# MCU.net
KiCad netlist of a schematic drawn in Altium Designer
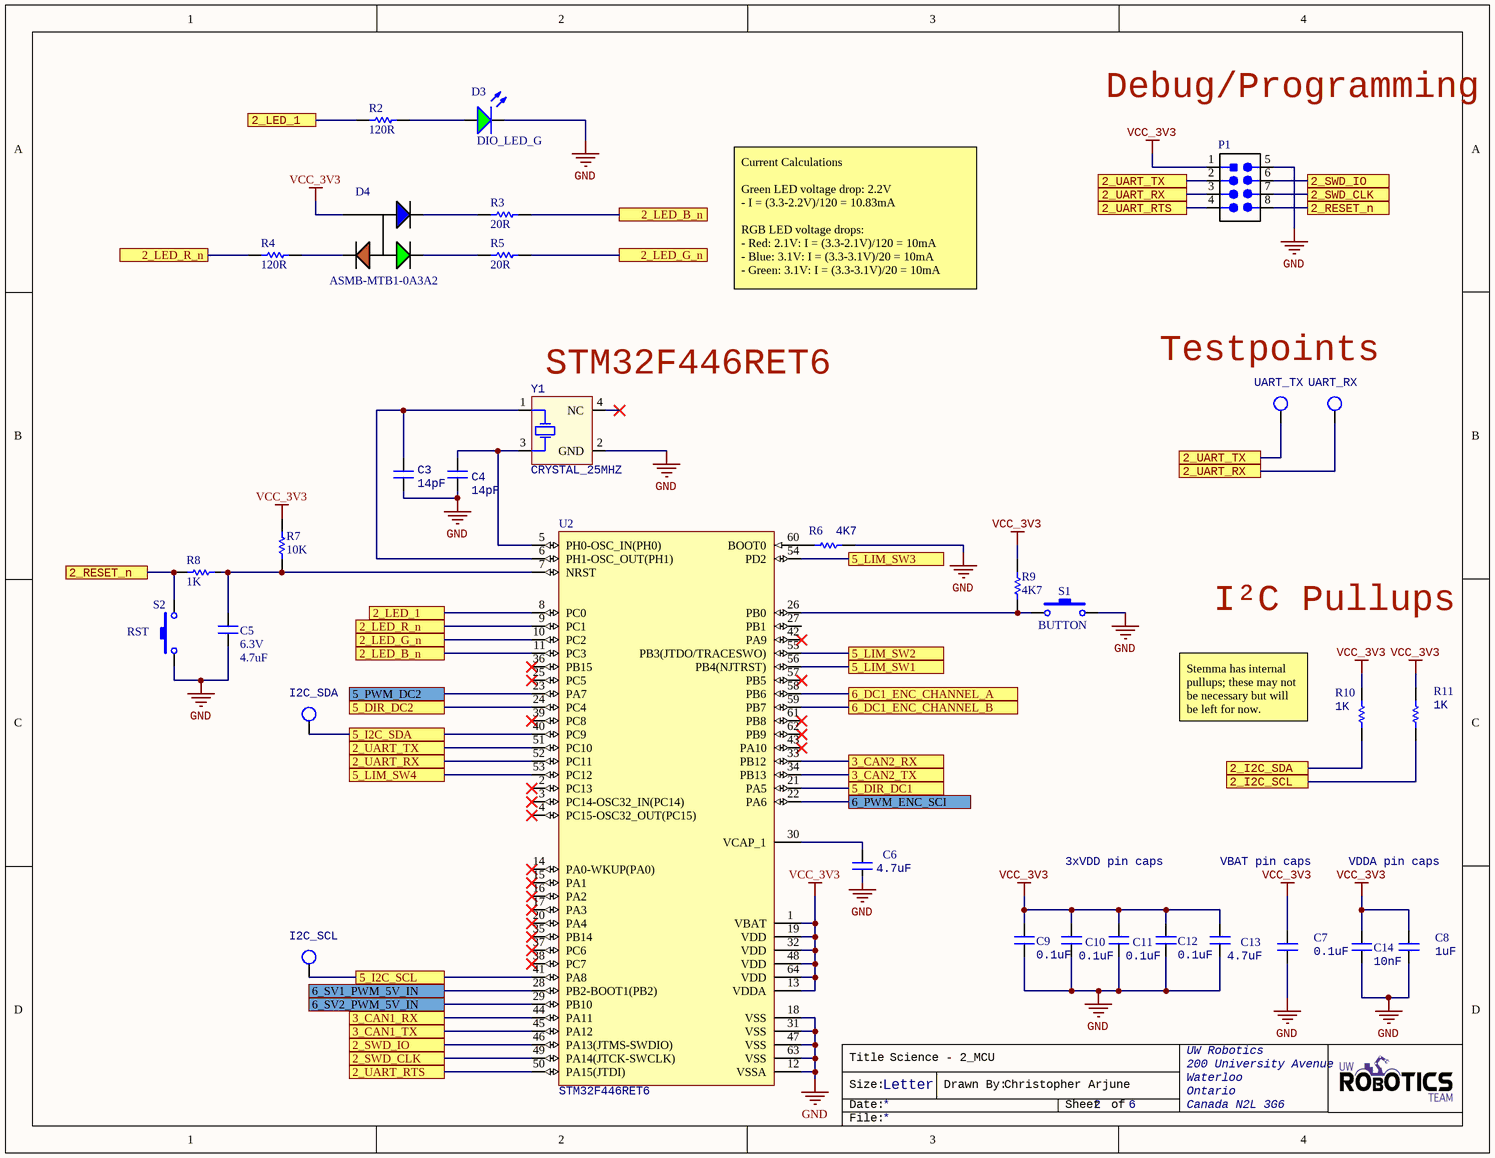
[diagram p0: MCU.SchDoc]

(export (version "E")
  (design (tool "Eeschema 10.0.6"))
  (components
    (comp (ref "C3")
      (value "14pF")
      (description "CAP CER 14PF 50V C0G/NP0 0603")
      (fields (field (name "TOLERANCE") "5%") (field (name "Comment") "CAP_14pF_50V_0603"))
      (libsource (lib "UWRT_Schematic_Library_2020") (part "CAP_14pF_50V_0603"))
    )
    (comp (ref "C4")
      (value "14pF")
      (description "CAP CER 14PF 50V C0G/NP0 0603")
      (fields (field (name "TOLERANCE") "5%") (field (name "Comment") "CAP_14pF_50V_0603"))
      (libsource (lib "UWRT_Schematic_Library_2020") (part "CAP_14pF_50V_0603"))
    )
    (comp (ref "C5")
      (value "4.7uF")
      (footprint "CAPC0603(1608)55_N")
      (description "CAP CER 4.7UF 6.3V X5R 0603")
      (fields (field (name "VOLTAGE RATING") "6.3V") (field (name "Comment") "CAP_4.7uF_0603"))
      (libsource (lib "UWRT_Schematic_Library_2020") (part "CAP_4.7uF_0603"))
    )
    (comp (ref "C6")
      (value "4.7uF")
      (footprint "CAPC0603(1608)55_N")
      (description "CAP CER 4.7UF 6.3V X5R 0603")
      (fields (field (name "MANUFACTURER") "Yageo") (field (name "MPN") "CC0603KRX5R5BB475"))
      (libsource (lib "UWRT_Schematic_Library_2020") (part "CAP_4.7uF_0603"))
    )
    (comp (ref "C7")
      (value "0.1uF")
      (footprint "CAPC0603(1608)55_N")
      (description "CAP CER 0.1UF 16V X7R 0603")
      (fields (field (name "MANUFACTURER") "Yageo") (field (name "MPN") "CC0603KRX7R7BB104"))
      (libsource (lib "UWRT_Schematic_Library_2020") (part "CAP_0.1uF_16V_0603"))
    )
    (comp (ref "C8")
      (value "1uF")
      (footprint "CAPC0603(1608)55_N")
      (description "CAP CER 1UF 16V Y5V 0603")
      (fields (field (name "MANUFACTURER") "Yageo") (field (name "MPN") "CC0603ZRY5V7BB105"))
      (libsource (lib "UWRT_Schematic_Library_2020") (part "CAP_1uF_16V_0603"))
    )
    (comp (ref "C9")
      (value "0.1uF")
      (footprint "CAPC0603(1608)55_N")
      (description "CAP CER 0.1UF 16V X7R 0603")
      (fields (field (name "MANUFACTURER") "Yageo") (field (name "MPN") "CC0603KRX7R7BB104"))
      (libsource (lib "UWRT_Schematic_Library_2020") (part "CAP_0.1uF_16V_0603"))
    )
    (comp (ref "C10")
      (value "0.1uF")
      (footprint "CAPC0603(1608)55_N")
      (description "CAP CER 0.1UF 16V X7R 0603")
      (fields (field (name "MANUFACTURER") "Yageo") (field (name "MPN") "CC0603KRX7R7BB104"))
      (libsource (lib "UWRT_Schematic_Library_2020") (part "CAP_0.1uF_16V_0603"))
    )
    (comp (ref "C11")
      (value "0.1uF")
      (footprint "CAPC0603(1608)55_N")
      (description "CAP CER 0.1UF 16V X7R 0603")
      (fields (field (name "MANUFACTURER") "Yageo") (field (name "MPN") "CC0603KRX7R7BB104"))
      (libsource (lib "UWRT_Schematic_Library_2020") (part "CAP_0.1uF_16V_0603"))
    )
    (comp (ref "C12")
      (value "0.1uF")
      (footprint "CAPC0603(1608)55_N")
      (description "CAP CER 0.1UF 16V X7R 0603")
      (fields (field (name "MANUFACTURER") "Yageo") (field (name "MPN") "CC0603KRX7R7BB104"))
      (libsource (lib "UWRT_Schematic_Library_2020") (part "CAP_0.1uF_16V_0603"))
    )
    (comp (ref "C13")
      (value "4.7uF")
      (footprint "CAPC0603(1608)55_N")
      (description "CAP CER 4.7UF 6.3V X5R 0603")
      (fields (field (name "MANUFACTURER") "Yageo") (field (name "MPN") "CC0603KRX5R5BB475"))
      (libsource (lib "UWRT_Schematic_Library_2020") (part "CAP_4.7uF_0603"))
    )
    (comp (ref "C14")
      (value "10nF")
      (footprint "CAPC0603(1608)55_N")
      (description "CAP CER 10000PF 16V X7R 0603")
      (fields (field (name "MANUFACTURER") "Yageo") (field (name "MPN") "CC0603KRX7R7BB103"))
      (libsource (lib "UWRT_Schematic_Library_2020") (part "CAP_10nF_0603"))
    )
    (comp (ref "D3")
      (value "DIO_LED_G")
      (footprint "LED_0805_LINE")
      (description "LED GREEN DIFFUSED 0805 SMD")
      (fields (field (name "MANUFACTURER") "OSRAM") (field (name "MPN") "LG R971-KN-1"))
      (libsource (lib "UWRT_Schematic_Library_2020") (part "DIO_LED_G"))
    )
    (comp (ref "D4")
      (value "LED_RGB")
      (footprint "LED_RGB")
      (description "LED RGB DIFFUSED 4PLCC SMD")
      (fields (field (name "MANUFACTURER PART NUMBER 1") "ASMB-MTB1-0A3A2"))
      (libsource (lib "UWRT_Schematic_Library_2020") (part "LED_RGB"))
    )
    (comp (ref "I2C_SCL")
      (value "TESTPOINT_LOOP")
      (footprint "TESTPOINT_LOOP")
      (description "Loop testpoint through-hole pad")
      (fields (field (name "MANUFACTURER") "Keystone Electronics"))
      (libsource (lib "UWRT_Schematic_Library_2020") (part "TESTPOINT_LOOP"))
    )
    (comp (ref "I2C_SDA")
      (value "TESTPOINT_LOOP")
      (footprint "TESTPOINT_LOOP")
      (description "Loop testpoint through-hole pad")
      (fields (field (name "MANUFACTURER") "Keystone Electronics"))
      (libsource (lib "UWRT_Schematic_Library_2020") (part "TESTPOINT_LOOP"))
    )
    (comp (ref "P1")
      (value "HEADER 4X2")
      (footprint "HEADER_2X4")
      (description "CONN HEADER VERT 8POS 2.54MM")
      (libsource (lib "UWRT_Schematic_Library_2020") (part "HEADER 4X2"))
    )
    (comp (ref "R2")
      (value "120R")
      (footprint "RESC0603(1608)_N")
      (description "RES SMD 120 OHM 5% 1/10W 0603")
      (fields (field (name "MANUFACTURER") "Yageo") (field (name "TOLERANCE") "5%"))
      (libsource (lib "UWRT_Schematic_Library_2020") (part "RES_120R_0603"))
    )
    (comp (ref "R3")
      (value "20R")
      (footprint "RESC0603(1608)_N")
      (description "RES SMD 20 OHM 5% 1/10W 0603")
      (fields (field (name "MANUFACTURER") "Yageo") (field (name "MPN") "RC0603JR-0720RL"))
      (libsource (lib "UWRT_Schematic_Library_2020") (part "RES_20R_0603"))
    )
    (comp (ref "R4")
      (value "120R")
      (footprint "RESC0603(1608)_N")
      (description "RES SMD 120 OHM 5% 1/10W 0603")
      (fields (field (name "MANUFACTURER") "Yageo") (field (name "MPN") "RC0603JR-07120RL"))
      (libsource (lib "UWRT_Schematic_Library_2020") (part "RES_120R_0603"))
    )
    (comp (ref "R5")
      (value "20R")
      (footprint "RESC0603(1608)_N")
      (description "RES SMD 20 OHM 5% 1/10W 0603")
      (fields (field (name "MANUFACTURER") "Yageo") (field (name "MPN") "RC0603JR-0720RL"))
      (libsource (lib "UWRT_Schematic_Library_2020") (part "RES_20R_0603"))
    )
    (comp (ref "R6")
      (value "4K7")
      (footprint "RESC0603(1608)_N")
      (description "RES SMD 4.7K OHM 5% 1/10W 0603")
      (fields (field (name "MANUFACTURER") "Yageo") (field (name "TOLERANCE") "5%"))
      (libsource (lib "UWRT_Schematic_Library_2020") (part "RES_4K7_0603"))
    )
    (comp (ref "R7")
      (value "10K")
      (footprint "RESC0603(1608)_N")
      (description "RES SMD 10K OHM 5% 1/10W 0603")
      (fields (field (name "TOLERANCE") "5%") (field (name "Comment") "RES_10K_0603"))
      (libsource (lib "UWRT_Schematic_Library_2020") (part "RES_10K_0603"))
    )
    (comp (ref "R8")
      (value "1K")
      (footprint "RESC0603(1608)_N")
      (description "RES SMD 1K OHM 5% 1/10W 0603")
      (fields (field (name "TOLERANCE") "5%") (field (name "Comment") "RES_1K_0603"))
      (libsource (lib "UWRT_Schematic_Library_2020") (part "RES_1K_0603"))
    )
    (comp (ref "R9")
      (value "4K7")
      (footprint "RESC0603(1608)_N")
      (description "RES SMD 4.7K OHM 5% 1/10W 0603")
      (fields (field (name "MANUFACTURER") "Yageo") (field (name "TOLERANCE") "5%"))
      (libsource (lib "UWRT_Schematic_Library_2020") (part "RES_4K7_0603"))
    )
    (comp (ref "R10")
      (value "1K")
      (footprint "RESC0603(1608)_N")
      (description "RES SMD 4.7K OHM 5% 1/10W 0603")
      (fields (field (name "MANUFACTURER") "Yageo") (field (name "TOLERANCE") "5%"))
      (libsource (lib "UWRT_Schematic_Library_2020") (part "RES_4K7_0603"))
    )
    (comp (ref "R11")
      (value "1K")
      (footprint "RESC0603(1608)_N")
      (description "RES SMD 4.7K OHM 5% 1/10W 0603")
      (fields (field (name "MANUFACTURER") "Yageo") (field (name "TOLERANCE") "5%"))
      (libsource (lib "UWRT_Schematic_Library_2020") (part "RES_4K7_0603"))
    )
    (comp (ref "S1")
      (value "BUTTON")
      (footprint "B3U-1100P")
      (description "Tactile Switch (Grey)")
      (fields (field (name "MPN") "B3U-1100P") (field (name "MANUFACTURER") "Omron Electronics Inc-EMC Div"))
      (libsource (lib "UWRT_Schematic_Library_2020") (part "SW_TACTILE"))
    )
    (comp (ref "S2")
      (value "RST")
      (footprint "PTS830GM140")
      (description "Power Switch (Red)")
      (fields (field (name "MPN") "PTS830GM140 SMTR LFS") (field (name "MANUFACTURER") "C&K"))
      (libsource (lib "UWRT_Schematic_Library_2020") (part "SW_PWR"))
    )
    (comp (ref "U2")
      (value "STM32F446RET6")
      (footprint "STM-LQFP64_L")
      (libsource (lib "UWRT_Schematic_Library_2020") (part "MCU_STM32F446RET6"))
    )
    (comp (ref "UART_RX")
      (value "TESTPOINT_LOOP")
      (footprint "TESTPOINT_LOOP")
      (description "Loop testpoint through-hole pad")
      (fields (field (name "MANUFACTURER") "Keystone Electronics"))
      (libsource (lib "UWRT_Schematic_Library_2020") (part "TESTPOINT_LOOP"))
    )
    (comp (ref "UART_TX")
      (value "TESTPOINT_LOOP")
      (footprint "TESTPOINT_LOOP")
      (description "Loop testpoint through-hole pad")
      (fields (field (name "MANUFACTURER") "Keystone Electronics"))
      (libsource (lib "UWRT_Schematic_Library_2020") (part "TESTPOINT_LOOP"))
    )
    (comp (ref "Y1")
      (value "CRYSTAL_25MHZ")
      (description "CRYSTAL 25.0000MHZ 12PF SMD")
      (libsource (lib "UWRT_Schematic_Library_2020") (part "CRYSTAL_25MHZ"))
    )
  )
  (nets
    (net (code "1") (name "/2_I2C_SCL") (class "Default")
      (node (ref "R11") (pin "1") (pinfunction "1_1") (pintype "passive"))
    )
    (net (code "2") (name "/2_I2C_SDA") (class "Default")
      (node (ref "R10") (pin "1") (pinfunction "1_1") (pintype "passive"))
    )
    (net (code "3") (name "/2_LED_1") (class "Default")
      (node (ref "R2") (pin "1") (pinfunction "1_1") (pintype "passive"))
      (node (ref "U2") (pin "8") (pinfunction "PC0_8") (pintype "bidirectional"))
    )
    (net (code "4") (name "/2_LED_B_n") (class "Default")
      (node (ref "R3") (pin "2") (pinfunction "2_2") (pintype "passive"))
      (node (ref "U2") (pin "11") (pinfunction "PC3_11") (pintype "bidirectional"))
    )
    (net (code "5") (name "/2_LED_G_n") (class "Default")
      (node (ref "R5") (pin "2") (pinfunction "2_2") (pintype "passive"))
      (node (ref "U2") (pin "10") (pinfunction "PC2_10") (pintype "bidirectional"))
    )
    (net (code "6") (name "/2_LED_R_n") (class "Default")
      (node (ref "R4") (pin "1") (pinfunction "1_1") (pintype "passive"))
      (node (ref "U2") (pin "9") (pinfunction "PC1_9") (pintype "bidirectional"))
    )
    (net (code "7") (name "/2_RESET_n") (class "Default")
      (node (ref "P1") (pin "8") (pinfunction "4_8") (pintype "passive"))
      (node (ref "R8") (pin "1") (pinfunction "1_1") (pintype "passive"))
      (node (ref "S2") (pin "2") (pinfunction "2_2") (pintype "passive"))
    )
    (net (code "8") (name "/2_SWD_CLK") (class "Default")
      (node (ref "P1") (pin "7") (pinfunction "3_7") (pintype "passive"))
      (node (ref "U2") (pin "49") (pinfunction "PA14(JTCK-SWCLK)_49") (pintype "bidirectional"))
    )
    (net (code "9") (name "/2_SWD_IO") (class "Default")
      (node (ref "P1") (pin "6") (pinfunction "2_6") (pintype "passive"))
      (node (ref "U2") (pin "46") (pinfunction "PA13(JTMS-SWDIO)_46") (pintype "bidirectional"))
    )
    (net (code "10") (name "/2_UART_RTS") (class "Default")
      (node (ref "P1") (pin "4") (pinfunction "4_4") (pintype "passive"))
      (node (ref "U2") (pin "50") (pinfunction "PA15(JTDI)_50") (pintype "bidirectional"))
    )
    (net (code "11") (name "/2_UART_RX") (class "Default")
      (node (ref "P1") (pin "3") (pinfunction "3_3") (pintype "passive"))
      (node (ref "U2") (pin "52") (pinfunction "PC11_52") (pintype "bidirectional"))
      (node (ref "UART_RX") (pin "1") (pintype "passive"))
    )
    (net (code "12") (name "/2_UART_TX") (class "Default")
      (node (ref "P1") (pin "2") (pinfunction "2_2") (pintype "passive"))
      (node (ref "U2") (pin "51") (pinfunction "PC10_51") (pintype "bidirectional"))
      (node (ref "UART_TX") (pin "1") (pintype "passive"))
    )
    (net (code "13") (name "/3_CAN1_RX") (class "Default")
      (node (ref "U2") (pin "44") (pinfunction "PA11_44") (pintype "bidirectional"))
    )
    (net (code "14") (name "/3_CAN1_TX") (class "Default")
      (node (ref "U2") (pin "45") (pinfunction "PA12_45") (pintype "bidirectional"))
    )
    (net (code "15") (name "/3_CAN2_RX") (class "Default")
      (node (ref "U2") (pin "33") (pinfunction "PB12_33") (pintype "bidirectional"))
    )
    (net (code "16") (name "/3_CAN2_TX") (class "Default")
      (node (ref "U2") (pin "34") (pinfunction "PB13_34") (pintype "bidirectional"))
    )
    (net (code "17") (name "/5_DIR_DC1") (class "Default")
      (node (ref "U2") (pin "21") (pinfunction "PA5_21") (pintype "bidirectional"))
    )
    (net (code "18") (name "/5_DIR_DC2") (class "Default")
      (node (ref "U2") (pin "24") (pinfunction "PC4_24") (pintype "bidirectional"))
    )
    (net (code "19") (name "/5_I2C_SCL") (class "Default")
      (node (ref "I2C_SCL") (pin "1") (pintype "passive"))
      (node (ref "U2") (pin "41") (pinfunction "PA8_41") (pintype "bidirectional"))
    )
    (net (code "20") (name "/5_I2C_SDA") (class "Default")
      (node (ref "I2C_SDA") (pin "1") (pintype "passive"))
      (node (ref "U2") (pin "40") (pinfunction "PC9_40") (pintype "bidirectional"))
    )
    (net (code "21") (name "/5_LIM_SW1") (class "Default")
      (node (ref "U2") (pin "56") (pinfunction "PB4(NJTRST)_56") (pintype "bidirectional"))
    )
    (net (code "22") (name "/5_LIM_SW2") (class "Default")
      (node (ref "U2") (pin "55") (pinfunction "PB3(JTDO/TRACESWO)_55") (pintype "bidirectional"))
    )
    (net (code "23") (name "/5_LIM_SW3") (class "Default")
      (node (ref "U2") (pin "54") (pinfunction "PD2_54") (pintype "bidirectional"))
    )
    (net (code "24") (name "/5_LIM_SW4") (class "Default")
      (node (ref "U2") (pin "53") (pinfunction "PC12_53") (pintype "bidirectional"))
    )
    (net (code "25") (name "/5_PWM_DC2") (class "Default")
      (node (ref "U2") (pin "23") (pinfunction "PA7_23") (pintype "bidirectional"))
    )
    (net (code "26") (name "/6_DC1_ENC_CHANNEL_A") (class "Default")
      (node (ref "U2") (pin "58") (pinfunction "PB6_58") (pintype "bidirectional"))
    )
    (net (code "27") (name "/6_DC1_ENC_CHANNEL_B") (class "Default")
      (node (ref "U2") (pin "59") (pinfunction "PB7_59") (pintype "bidirectional"))
    )
    (net (code "28") (name "/6_PWM_ENC_SCI") (class "Default")
      (node (ref "U2") (pin "22") (pinfunction "PA6_22") (pintype "bidirectional"))
    )
    (net (code "29") (name "/6_SV1_PWM_5V_IN") (class "Default")
      (node (ref "U2") (pin "28") (pinfunction "PB2-BOOT1(PB2)_28") (pintype "bidirectional"))
    )
    (net (code "30") (name "/6_SV2_PWM_5V_IN") (class "Default")
      (node (ref "U2") (pin "29") (pinfunction "PB10_29") (pintype "bidirectional"))
    )
    (net (code "31") (name "GND") (class "Default")
      (node (ref "C10") (pin "1") (pinfunction "1_1") (pintype "passive"))
      (node (ref "C11") (pin "1") (pinfunction "1_1") (pintype "passive"))
      (node (ref "C12") (pin "1") (pinfunction "1_1") (pintype "passive"))
      (node (ref "C13") (pin "1") (pinfunction "1_1") (pintype "passive"))
      (node (ref "C14") (pin "1") (pinfunction "1_1") (pintype "passive"))
      (node (ref "C3") (pin "1") (pinfunction "1_1") (pintype "passive"))
      (node (ref "C4") (pin "1") (pinfunction "1_1") (pintype "passive"))
      (node (ref "C5") (pin "2") (pinfunction "2_2") (pintype "passive"))
      (node (ref "C6") (pin "1") (pinfunction "1_1") (pintype "passive"))
      (node (ref "C7") (pin "1") (pinfunction "1_1") (pintype "passive"))
      (node (ref "C8") (pin "1") (pinfunction "1_1") (pintype "passive"))
      (node (ref "C9") (pin "1") (pinfunction "1_1") (pintype "passive"))
      (node (ref "D3") (pin "2") (pinfunction "K_2") (pintype "passive"))
      (node (ref "P1") (pin "5") (pinfunction "GND_5") (pintype "passive"))
      (node (ref "R6") (pin "1") (pinfunction "1_1") (pintype "passive"))
      (node (ref "S1") (pin "2") (pinfunction "2_2") (pintype "passive"))
      (node (ref "S2") (pin "1") (pinfunction "1_1") (pintype "passive"))
      (node (ref "U2") (pin "12") (pinfunction "VSSA_12") (pintype "power_in"))
      (node (ref "U2") (pin "18") (pinfunction "VSS_18") (pintype "power_in"))
      (node (ref "U2") (pin "31") (pinfunction "VSS_31") (pintype "power_in"))
      (node (ref "U2") (pin "47") (pinfunction "VSS_47") (pintype "power_in"))
      (node (ref "U2") (pin "63") (pinfunction "VSS_63") (pintype "power_in"))
      (node (ref "Y1") (pin "2") (pinfunction "GND_2") (pintype "power_in"))
    )
    (net (code "32") (name "Net-(D3-A)") (class "Default")
      (node (ref "D3") (pin "1") (pinfunction "A_1") (pintype "passive"))
      (node (ref "R2") (pin "2") (pinfunction "2_2") (pintype "passive"))
    )
    (net (code "33") (name "Net-(D4-10)") (class "Default")
      (node (ref "D4") (pin "3") (pinfunction "10_3") (pintype "passive"))
      (node (ref "R3") (pin "1") (pinfunction "1_1") (pintype "passive"))
    )
    (net (code "34") (name "Net-(D4-11)") (class "Default")
      (node (ref "D4") (pin "1") (pinfunction "11_1") (pintype "passive"))
      (node (ref "R4") (pin "2") (pinfunction "2_2") (pintype "passive"))
    )
    (net (code "35") (name "Net-(D4-12)") (class "Default")
      (node (ref "D4") (pin "2") (pinfunction "12_2") (pintype "passive"))
      (node (ref "R5") (pin "1") (pinfunction "1_1") (pintype "passive"))
    )
    (net (code "36") (name "Net-(U2-BOOT0)") (class "Default")
      (node (ref "R6") (pin "2") (pinfunction "2_2") (pintype "passive"))
      (node (ref "U2") (pin "60") (pinfunction "BOOT0_60") (pintype "input"))
    )
    (net (code "37") (name "Net-(U2-NRST)") (class "Default")
      (node (ref "C5") (pin "1") (pinfunction "1_1") (pintype "passive"))
      (node (ref "R7") (pin "1") (pinfunction "1_1") (pintype "passive"))
      (node (ref "R8") (pin "2") (pinfunction "2_2") (pintype "passive"))
      (node (ref "U2") (pin "7") (pinfunction "NRST_7") (pintype "bidirectional"))
    )
    (net (code "38") (name "Net-(U2-PB0)") (class "Default")
      (node (ref "R9") (pin "2") (pinfunction "2_2") (pintype "passive"))
      (node (ref "S1") (pin "1") (pinfunction "1_1") (pintype "passive"))
      (node (ref "U2") (pin "26") (pinfunction "PB0_26") (pintype "bidirectional"))
    )
    (net (code "39") (name "Net-(U2-PH0-OSC_IN(PH0))") (class "Default")
      (node (ref "C4") (pin "2") (pinfunction "2_2") (pintype "passive"))
      (node (ref "U2") (pin "5") (pinfunction "PH0-OSC_IN(PH0)_5") (pintype "bidirectional"))
      (node (ref "Y1") (pin "3") (pinfunction "HOT_3") (pintype "passive"))
    )
    (net (code "40") (name "Net-(U2-PH1-OSC_OUT(PH1))") (class "Default")
      (node (ref "C3") (pin "2") (pinfunction "2_2") (pintype "passive"))
      (node (ref "U2") (pin "6") (pinfunction "PH1-OSC_OUT(PH1)_6") (pintype "bidirectional"))
      (node (ref "Y1") (pin "1") (pinfunction "HOT_1") (pintype "passive"))
    )
    (net (code "41") (name "Net-(U2-VCAP_1)") (class "Default")
      (node (ref "C6") (pin "2") (pinfunction "2_2") (pintype "passive"))
      (node (ref "U2") (pin "30") (pinfunction "VCAP_1_30") (pintype "passive"))
    )
    (net (code "42") (name "VCC_3V3") (class "Default")
      (node (ref "C10") (pin "2") (pinfunction "2_2") (pintype "passive"))
      (node (ref "C11") (pin "2") (pinfunction "2_2") (pintype "passive"))
      (node (ref "C12") (pin "2") (pinfunction "2_2") (pintype "passive"))
      (node (ref "C13") (pin "2") (pinfunction "2_2") (pintype "passive"))
      (node (ref "C14") (pin "2") (pinfunction "2_2") (pintype "passive"))
      (node (ref "C7") (pin "2") (pinfunction "2_2") (pintype "passive"))
      (node (ref "C8") (pin "2") (pinfunction "2_2") (pintype "passive"))
      (node (ref "C9") (pin "2") (pinfunction "2_2") (pintype "passive"))
      (node (ref "D4") (pin "4") (pinfunction "9_4") (pintype "passive"))
      (node (ref "P1") (pin "1") (pinfunction "VCC_1") (pintype "passive"))
      (node (ref "R10") (pin "2") (pinfunction "2_2") (pintype "passive"))
      (node (ref "R11") (pin "2") (pinfunction "2_2") (pintype "passive"))
      (node (ref "R7") (pin "2") (pinfunction "2_2") (pintype "passive"))
      (node (ref "R9") (pin "1") (pinfunction "1_1") (pintype "passive"))
      (node (ref "U2") (pin "1") (pinfunction "VBAT_1") (pintype "power_in"))
      (node (ref "U2") (pin "13") (pinfunction "VDDA_13") (pintype "power_in"))
      (node (ref "U2") (pin "19") (pinfunction "VDD_19") (pintype "power_in"))
      (node (ref "U2") (pin "32") (pinfunction "VDD_32") (pintype "power_in"))
      (node (ref "U2") (pin "48") (pinfunction "VDD_48") (pintype "power_in"))
      (node (ref "U2") (pin "64") (pinfunction "VDD_64") (pintype "power_in"))
    )
    (net (code "43") (name "unconnected-(U2-PA0-WKUP(PA0)-Pad14)") (class "Default")
      (node (ref "U2") (pin "14") (pinfunction "PA0-WKUP(PA0)_14") (pintype "bidirectional+no_connect"))
    )
    (net (code "44") (name "unconnected-(U2-PA1-Pad15)") (class "Default")
      (node (ref "U2") (pin "15") (pinfunction "PA1_15") (pintype "bidirectional+no_connect"))
    )
    (net (code "45") (name "unconnected-(U2-PA2-Pad16)") (class "Default")
      (node (ref "U2") (pin "16") (pinfunction "PA2_16") (pintype "bidirectional+no_connect"))
    )
    (net (code "46") (name "unconnected-(U2-PA3-Pad17)") (class "Default")
      (node (ref "U2") (pin "17") (pinfunction "PA3_17") (pintype "bidirectional+no_connect"))
    )
    (net (code "47") (name "unconnected-(U2-PA4-Pad20)") (class "Default")
      (node (ref "U2") (pin "20") (pinfunction "PA4_20") (pintype "bidirectional+no_connect"))
    )
    (net (code "48") (name "unconnected-(U2-PA9-Pad42)") (class "Default")
      (node (ref "U2") (pin "42") (pinfunction "PA9_42") (pintype "bidirectional+no_connect"))
    )
    (net (code "49") (name "unconnected-(U2-PA10-Pad43)") (class "Default")
      (node (ref "U2") (pin "43") (pinfunction "PA10_43") (pintype "bidirectional+no_connect"))
    )
    (net (code "50") (name "unconnected-(U2-PB1-Pad27)") (class "Default")
      (node (ref "U2") (pin "27") (pinfunction "PB1_27") (pintype "bidirectional"))
    )
    (net (code "51") (name "unconnected-(U2-PB5-Pad57)") (class "Default")
      (node (ref "U2") (pin "57") (pinfunction "PB5_57") (pintype "bidirectional+no_connect"))
    )
    (net (code "52") (name "unconnected-(U2-PB8-Pad61)") (class "Default")
      (node (ref "U2") (pin "61") (pinfunction "PB8_61") (pintype "bidirectional+no_connect"))
    )
    (net (code "53") (name "unconnected-(U2-PB9-Pad62)") (class "Default")
      (node (ref "U2") (pin "62") (pinfunction "PB9_62") (pintype "bidirectional+no_connect"))
    )
    (net (code "54") (name "unconnected-(U2-PB14-Pad35)") (class "Default")
      (node (ref "U2") (pin "35") (pinfunction "PB14_35") (pintype "bidirectional+no_connect"))
    )
    (net (code "55") (name "unconnected-(U2-PB15-Pad36)") (class "Default")
      (node (ref "U2") (pin "36") (pinfunction "PB15_36") (pintype "bidirectional+no_connect"))
    )
    (net (code "56") (name "unconnected-(U2-PC5-Pad25)") (class "Default")
      (node (ref "U2") (pin "25") (pinfunction "PC5_25") (pintype "bidirectional+no_connect"))
    )
    (net (code "57") (name "unconnected-(U2-PC6-Pad37)") (class "Default")
      (node (ref "U2") (pin "37") (pinfunction "PC6_37") (pintype "bidirectional+no_connect"))
    )
    (net (code "58") (name "unconnected-(U2-PC7-Pad38)") (class "Default")
      (node (ref "U2") (pin "38") (pinfunction "PC7_38") (pintype "bidirectional+no_connect"))
    )
    (net (code "59") (name "unconnected-(U2-PC8-Pad39)") (class "Default")
      (node (ref "U2") (pin "39") (pinfunction "PC8_39") (pintype "bidirectional+no_connect"))
    )
    (net (code "60") (name "unconnected-(U2-PC13-Pad2)") (class "Default")
      (node (ref "U2") (pin "2") (pinfunction "PC13_2") (pintype "bidirectional+no_connect"))
    )
    (net (code "61") (name "unconnected-(U2-PC14-OSC32_IN(PC14)-Pad3)") (class "Default")
      (node (ref "U2") (pin "3") (pinfunction "PC14-OSC32_IN(PC14)_3") (pintype "bidirectional+no_connect"))
    )
    (net (code "62") (name "unconnected-(U2-PC15-OSC32_OUT(PC15)-Pad4)") (class "Default")
      (node (ref "U2") (pin "4") (pinfunction "PC15-OSC32_OUT(PC15)_4") (pintype "bidirectional+no_connect"))
    )
    (net (code "63") (name "unconnected-(Y1-NC-Pad4)") (class "Default")
      (node (ref "Y1") (pin "4") (pinfunction "NC_4") (pintype "passive+no_connect"))
    )
  )
)
